# pcb_inverter_final.net
KiCad netlist of a schematic drawn in EAGLE
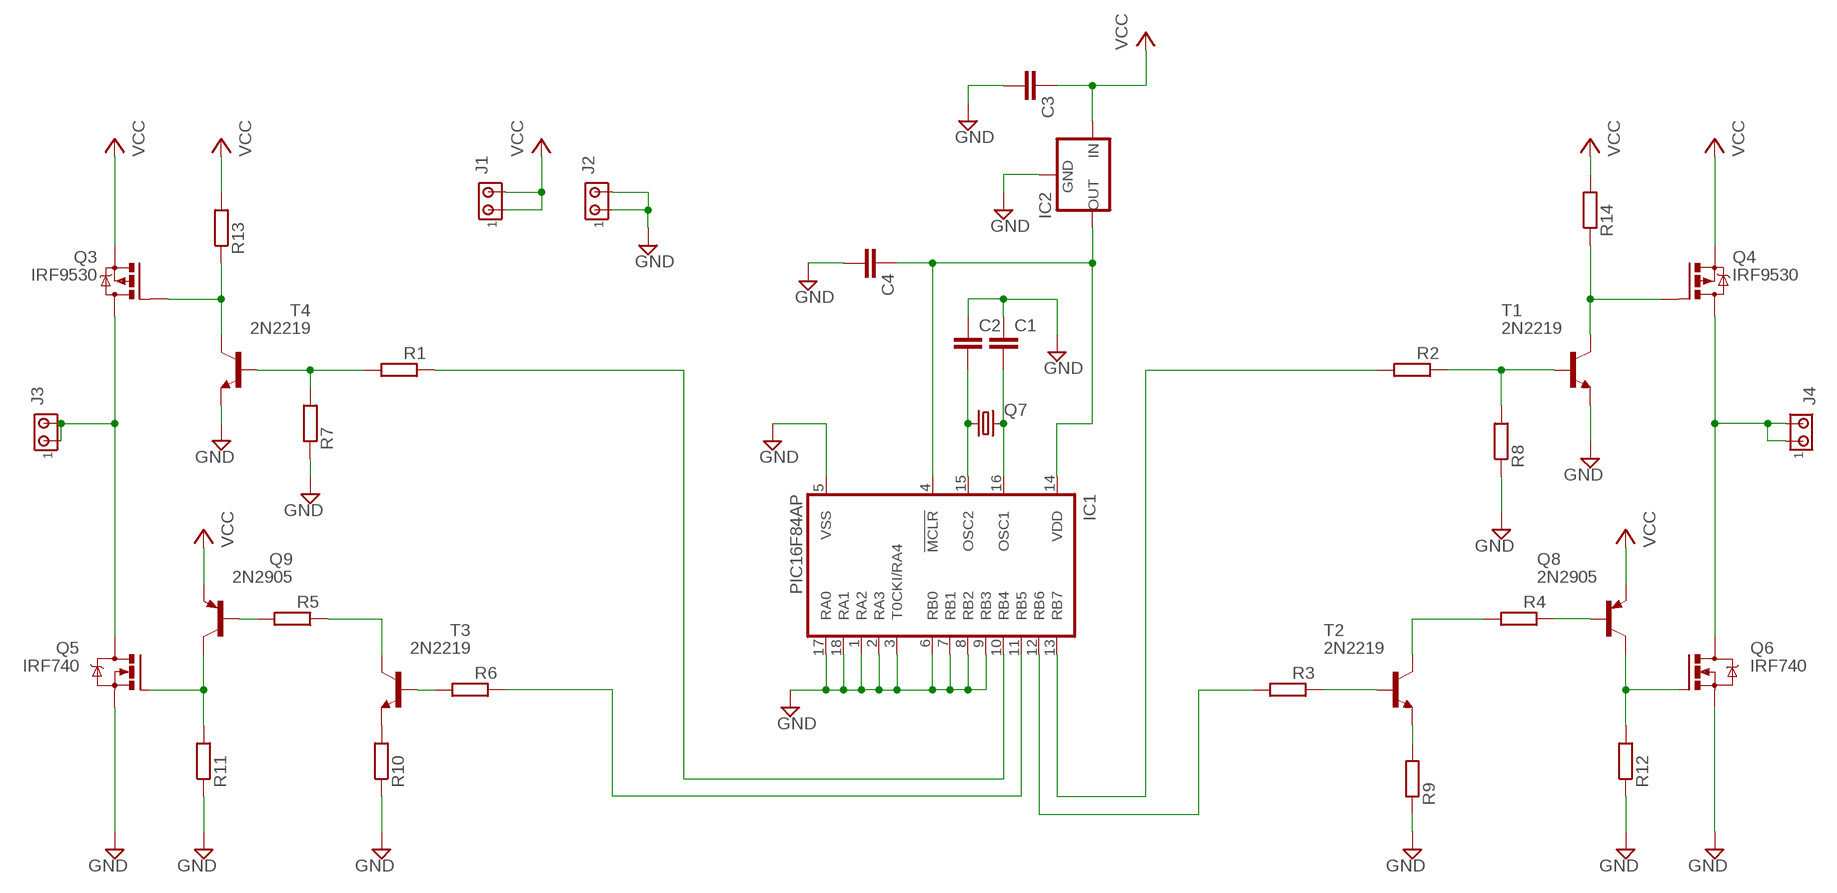
[diagram p0: schematic, sheet 1]

(export (version "E")
  (design (tool "Eeschema 10.0.6"))
  (components
    (comp (ref "C1")
      (value "C2.5/5")
      (footprint "eagle-import:C2.5-5")
      (libsource (lib "eagle-import") (part "C2.5/5"))
    )
    (comp (ref "C2")
      (value "C2.5/5")
      (footprint "eagle-import:C2.5-5")
      (libsource (lib "eagle-import") (part "C2.5/5"))
    )
    (comp (ref "C3")
      (value "C2.5/5")
      (footprint "eagle-import:C2.5-5")
      (libsource (lib "eagle-import") (part "C2.5/5"))
    )
    (comp (ref "C4")
      (value "C2.5/5")
      (footprint "eagle-import:C2.5-5")
      (libsource (lib "eagle-import") (part "C2.5/5"))
    )
    (comp (ref "IC1")
      (value "PIC16F84AP")
      (footprint "eagle-import:DIL18")
      (fields (field (name "MF") "MICROCHIP") (field (name "MPN") "PIC16F84A-04I/P"))
      (libsource (lib "eagle-import") (part "PIC16F8P4A"))
    )
    (comp (ref "IC2")
      (value "78XXS")
      (footprint "eagle-import:78XXS")
      (libsource (lib "eagle-import") (part "78XXS"))
    )
    (comp (ref "J1")
      (value "MTA02-156")
      (footprint "eagle-import:1X2MTA")
      (libsource (lib "eagle-import") (part "MTA02-156"))
    )
    (comp (ref "J2")
      (value "MTA02-156")
      (footprint "eagle-import:1X2MTA")
      (libsource (lib "eagle-import") (part "MTA02-156"))
    )
    (comp (ref "J3")
      (value "MTA02-156")
      (footprint "eagle-import:1X2MTA")
      (libsource (lib "eagle-import") (part "MTA02-156"))
    )
    (comp (ref "J4")
      (value "MTA02-156")
      (footprint "eagle-import:1X2MTA")
      (libsource (lib "eagle-import") (part "MTA02-156"))
    )
    (comp (ref "Q3")
      (value "IRF9530")
      (footprint "eagle-import:TO220BV")
      (libsource (lib "eagle-import") (part "IRF9530"))
    )
    (comp (ref "Q4")
      (value "IRF9530")
      (footprint "eagle-import:TO220BV")
      (libsource (lib "eagle-import") (part "IRF9530"))
    )
    (comp (ref "Q5")
      (value "IRF740")
      (footprint "eagle-import:TO220BV")
      (libsource (lib "eagle-import") (part "IRF740"))
    )
    (comp (ref "Q6")
      (value "IRF740")
      (footprint "eagle-import:TO220BV")
      (libsource (lib "eagle-import") (part "IRF740"))
    )
    (comp (ref "Q7")
      (value "CRYSTALHC18U-V")
      (footprint "eagle-import:HC18U-V")
      (libsource (lib "eagle-import") (part "CRYSTALHC18U-V"))
    )
    (comp (ref "Q8")
      (value "2N2905")
      (footprint "eagle-import:TO5")
      (libsource (lib "eagle-import") (part "2N2905"))
    )
    (comp (ref "Q9")
      (value "2N2905")
      (footprint "eagle-import:TO5")
      (libsource (lib "eagle-import") (part "2N2905"))
    )
    (comp (ref "R1")
      (value "R-EU_0204/7")
      (footprint "eagle-import:0204_7")
      (libsource (lib "eagle-import") (part "R-EU_0204/7"))
    )
    (comp (ref "R2")
      (value "R-EU_0204/7")
      (footprint "eagle-import:0204_7")
      (libsource (lib "eagle-import") (part "R-EU_0204/7"))
    )
    (comp (ref "R3")
      (value "R-EU_0204/7")
      (footprint "eagle-import:0204_7")
      (libsource (lib "eagle-import") (part "R-EU_0204/7"))
    )
    (comp (ref "R4")
      (value "R-EU_0204/7")
      (footprint "eagle-import:0204_7")
      (libsource (lib "eagle-import") (part "R-EU_0204/7"))
    )
    (comp (ref "R5")
      (value "R-EU_0204/7")
      (footprint "eagle-import:0204_7")
      (libsource (lib "eagle-import") (part "R-EU_0204/7"))
    )
    (comp (ref "R6")
      (value "R-EU_0204/7")
      (footprint "eagle-import:0204_7")
      (libsource (lib "eagle-import") (part "R-EU_0204/7"))
    )
    (comp (ref "R7")
      (value "R-EU_0204/7")
      (footprint "eagle-import:0204_7")
      (libsource (lib "eagle-import") (part "R-EU_0204/7"))
    )
    (comp (ref "R8")
      (value "R-EU_0204/7")
      (footprint "eagle-import:0204_7")
      (libsource (lib "eagle-import") (part "R-EU_0204/7"))
    )
    (comp (ref "R9")
      (value "R-EU_0204/7")
      (footprint "eagle-import:0204_7")
      (libsource (lib "eagle-import") (part "R-EU_0204/7"))
    )
    (comp (ref "R10")
      (value "R-EU_0204/7")
      (footprint "eagle-import:0204_7")
      (libsource (lib "eagle-import") (part "R-EU_0204/7"))
    )
    (comp (ref "R11")
      (value "R-EU_0204/7")
      (footprint "eagle-import:0204_7")
      (libsource (lib "eagle-import") (part "R-EU_0204/7"))
    )
    (comp (ref "R12")
      (value "R-EU_0204/7")
      (footprint "eagle-import:0204_7")
      (libsource (lib "eagle-import") (part "R-EU_0204/7"))
    )
    (comp (ref "R13")
      (value "R-EU_0204/7")
      (footprint "eagle-import:0204_7")
      (libsource (lib "eagle-import") (part "R-EU_0204/7"))
    )
    (comp (ref "R14")
      (value "R-EU_0204/7")
      (footprint "eagle-import:0204_7")
      (libsource (lib "eagle-import") (part "R-EU_0204/7"))
    )
    (comp (ref "T1")
      (value "2N2219")
      (footprint "eagle-import:TO5")
      (libsource (lib "eagle-import") (part "2N2219"))
    )
    (comp (ref "T2")
      (value "2N2219")
      (footprint "eagle-import:TO5")
      (libsource (lib "eagle-import") (part "2N2219"))
    )
    (comp (ref "T3")
      (value "2N2219")
      (footprint "eagle-import:TO5")
      (libsource (lib "eagle-import") (part "2N2219"))
    )
    (comp (ref "T4")
      (value "2N2219")
      (footprint "eagle-import:TO5")
      (libsource (lib "eagle-import") (part "2N2219"))
    )
  )
  (nets
    (net (code "1") (name "GND") (class "Default")
      (node (ref "C1") (pin "1") (pinfunction "1_1") (pintype "passive"))
      (node (ref "C2") (pin "1") (pinfunction "1_1") (pintype "passive"))
      (node (ref "C3") (pin "2") (pinfunction "2_2") (pintype "passive"))
      (node (ref "C4") (pin "2") (pinfunction "2_2") (pintype "passive"))
      (node (ref "IC1") (pin "1") (pinfunction "RA2_1") (pintype "bidirectional"))
      (node (ref "IC1") (pin "17") (pinfunction "RA0_17") (pintype "bidirectional"))
      (node (ref "IC1") (pin "18") (pinfunction "RA1_18") (pintype "bidirectional"))
      (node (ref "IC1") (pin "2") (pinfunction "RA3_2") (pintype "bidirectional"))
      (node (ref "IC1") (pin "3") (pinfunction "T0CKI/RA4_3") (pintype "bidirectional"))
      (node (ref "IC1") (pin "5") (pinfunction "VSS_5") (pintype "power_in"))
      (node (ref "IC1") (pin "6") (pinfunction "RB0_6") (pintype "bidirectional"))
      (node (ref "IC1") (pin "7") (pinfunction "RB1_7") (pintype "bidirectional"))
      (node (ref "IC1") (pin "8") (pinfunction "RB2_8") (pintype "bidirectional"))
      (node (ref "IC1") (pin "9") (pinfunction "RB3_9") (pintype "bidirectional"))
      (node (ref "IC2") (pin "GND") (pinfunction "GND_GND") (pintype "input"))
      (node (ref "J2") (pin "1") (pinfunction "1_1") (pintype "passive"))
      (node (ref "J2") (pin "2") (pinfunction "2_2") (pintype "passive"))
      (node (ref "Q5") (pin "S") (pinfunction "S_S") (pintype "passive"))
      (node (ref "Q6") (pin "S") (pinfunction "S_S") (pintype "passive"))
      (node (ref "R10") (pin "1") (pinfunction "1_1") (pintype "passive"))
      (node (ref "R11") (pin "1") (pinfunction "1_1") (pintype "passive"))
      (node (ref "R12") (pin "1") (pinfunction "1_1") (pintype "passive"))
      (node (ref "R7") (pin "1") (pinfunction "1_1") (pintype "passive"))
      (node (ref "R8") (pin "1") (pinfunction "1_1") (pintype "passive"))
      (node (ref "R9") (pin "1") (pinfunction "1_1") (pintype "passive"))
      (node (ref "T1") (pin "1") (pinfunction "E_1") (pintype "passive"))
      (node (ref "T4") (pin "1") (pinfunction "E_1") (pintype "passive"))
    )
    (net (code "2") (name "Net-(IC1-OSC1)") (class "Default")
      (node (ref "C1") (pin "2") (pinfunction "2_2") (pintype "passive"))
      (node (ref "IC1") (pin "16") (pinfunction "OSC1_16") (pintype "input"))
      (node (ref "Q7") (pin "2") (pinfunction "2_2") (pintype "passive"))
    )
    (net (code "3") (name "Net-(IC1-OSC2)") (class "Default")
      (node (ref "C2") (pin "2") (pinfunction "2_2") (pintype "passive"))
      (node (ref "IC1") (pin "15") (pinfunction "OSC2_15") (pintype "output"))
      (node (ref "Q7") (pin "1") (pinfunction "1_1") (pintype "passive"))
    )
    (net (code "4") (name "Net-(IC1-RB4)") (class "Default")
      (node (ref "IC1") (pin "10") (pinfunction "RB4_10") (pintype "bidirectional"))
      (node (ref "R1") (pin "1") (pinfunction "1_1") (pintype "passive"))
    )
    (net (code "5") (name "Net-(IC1-RB5)") (class "Default")
      (node (ref "IC1") (pin "11") (pinfunction "RB5_11") (pintype "bidirectional"))
      (node (ref "R6") (pin "1") (pinfunction "1_1") (pintype "passive"))
    )
    (net (code "6") (name "Net-(IC1-RB6)") (class "Default")
      (node (ref "IC1") (pin "12") (pinfunction "RB6_12") (pintype "bidirectional"))
      (node (ref "R3") (pin "2") (pinfunction "2_2") (pintype "passive"))
    )
    (net (code "7") (name "Net-(IC1-RB7)") (class "Default")
      (node (ref "IC1") (pin "13") (pinfunction "RB7_13") (pintype "bidirectional"))
      (node (ref "R2") (pin "2") (pinfunction "2_2") (pintype "passive"))
    )
    (net (code "8") (name "Net-(IC1-VDD)") (class "Default")
      (node (ref "C4") (pin "1") (pinfunction "1_1") (pintype "passive"))
      (node (ref "IC1") (pin "14") (pinfunction "VDD_14") (pintype "power_in"))
      (node (ref "IC1") (pin "4") (pinfunction "~{MCLR}_4") (pintype "input"))
      (node (ref "IC2") (pin "OUT") (pinfunction "OUT_OUT") (pintype "passive"))
    )
    (net (code "9") (name "Net-(J3-Pad1)") (class "Default")
      (node (ref "J3") (pin "1") (pinfunction "1_1") (pintype "passive"))
      (node (ref "J3") (pin "2") (pinfunction "2_2") (pintype "passive"))
      (node (ref "Q3") (pin "D") (pinfunction "D_D") (pintype "passive"))
      (node (ref "Q5") (pin "D") (pinfunction "D_D") (pintype "passive"))
    )
    (net (code "10") (name "Net-(J4-Pad1)") (class "Default")
      (node (ref "J4") (pin "1") (pinfunction "1_1") (pintype "passive"))
      (node (ref "J4") (pin "2") (pinfunction "2_2") (pintype "passive"))
      (node (ref "Q4") (pin "D") (pinfunction "D_D") (pintype "passive"))
      (node (ref "Q6") (pin "D") (pinfunction "D_D") (pintype "passive"))
    )
    (net (code "11") (name "Net-(Q8-B)") (class "Default")
      (node (ref "Q8") (pin "2") (pinfunction "B_2") (pintype "passive"))
      (node (ref "R4") (pin "1") (pinfunction "1_1") (pintype "passive"))
    )
    (net (code "12") (name "Net-(Q8-C)") (class "Default")
      (node (ref "Q6") (pin "G") (pinfunction "G_G") (pintype "passive"))
      (node (ref "Q8") (pin "3") (pinfunction "C_3") (pintype "passive"))
      (node (ref "R12") (pin "2") (pinfunction "2_2") (pintype "passive"))
    )
    (net (code "13") (name "Net-(Q9-B)") (class "Default")
      (node (ref "Q9") (pin "2") (pinfunction "B_2") (pintype "passive"))
      (node (ref "R5") (pin "2") (pinfunction "2_2") (pintype "passive"))
    )
    (net (code "14") (name "Net-(Q9-C)") (class "Default")
      (node (ref "Q5") (pin "G") (pinfunction "G_G") (pintype "passive"))
      (node (ref "Q9") (pin "3") (pinfunction "C_3") (pintype "passive"))
      (node (ref "R11") (pin "2") (pinfunction "2_2") (pintype "passive"))
    )
    (net (code "15") (name "Net-(T1-B)") (class "Default")
      (node (ref "R2") (pin "1") (pinfunction "1_1") (pintype "passive"))
      (node (ref "R8") (pin "2") (pinfunction "2_2") (pintype "passive"))
      (node (ref "T1") (pin "2") (pinfunction "B_2") (pintype "passive"))
    )
    (net (code "16") (name "Net-(T1-C)") (class "Default")
      (node (ref "Q4") (pin "G") (pinfunction "G_G") (pintype "passive"))
      (node (ref "R14") (pin "1") (pinfunction "1_1") (pintype "passive"))
      (node (ref "T1") (pin "3") (pinfunction "C_3") (pintype "passive"))
    )
    (net (code "17") (name "Net-(T2-B)") (class "Default")
      (node (ref "R3") (pin "1") (pinfunction "1_1") (pintype "passive"))
      (node (ref "T2") (pin "2") (pinfunction "B_2") (pintype "passive"))
    )
    (net (code "18") (name "Net-(T2-C)") (class "Default")
      (node (ref "R4") (pin "2") (pinfunction "2_2") (pintype "passive"))
      (node (ref "T2") (pin "3") (pinfunction "C_3") (pintype "passive"))
    )
    (net (code "19") (name "Net-(T2-E)") (class "Default")
      (node (ref "R9") (pin "2") (pinfunction "2_2") (pintype "passive"))
      (node (ref "T2") (pin "1") (pinfunction "E_1") (pintype "passive"))
    )
    (net (code "20") (name "Net-(T3-B)") (class "Default")
      (node (ref "R6") (pin "2") (pinfunction "2_2") (pintype "passive"))
      (node (ref "T3") (pin "2") (pinfunction "B_2") (pintype "passive"))
    )
    (net (code "21") (name "Net-(T3-C)") (class "Default")
      (node (ref "R5") (pin "1") (pinfunction "1_1") (pintype "passive"))
      (node (ref "T3") (pin "3") (pinfunction "C_3") (pintype "passive"))
    )
    (net (code "22") (name "Net-(T3-E)") (class "Default")
      (node (ref "R10") (pin "2") (pinfunction "2_2") (pintype "passive"))
      (node (ref "T3") (pin "1") (pinfunction "E_1") (pintype "passive"))
    )
    (net (code "23") (name "Net-(T4-B)") (class "Default")
      (node (ref "R1") (pin "2") (pinfunction "2_2") (pintype "passive"))
      (node (ref "R7") (pin "2") (pinfunction "2_2") (pintype "passive"))
      (node (ref "T4") (pin "2") (pinfunction "B_2") (pintype "passive"))
    )
    (net (code "24") (name "Net-(T4-C)") (class "Default")
      (node (ref "Q3") (pin "G") (pinfunction "G_G") (pintype "passive"))
      (node (ref "R13") (pin "1") (pinfunction "1_1") (pintype "passive"))
      (node (ref "T4") (pin "3") (pinfunction "C_3") (pintype "passive"))
    )
    (net (code "25") (name "VCC") (class "Default")
      (node (ref "C3") (pin "1") (pinfunction "1_1") (pintype "passive"))
      (node (ref "IC2") (pin "IN") (pinfunction "IN_IN") (pintype "input"))
      (node (ref "J1") (pin "1") (pinfunction "1_1") (pintype "passive"))
      (node (ref "J1") (pin "2") (pinfunction "2_2") (pintype "passive"))
      (node (ref "Q3") (pin "S") (pinfunction "S_S") (pintype "passive"))
      (node (ref "Q4") (pin "S") (pinfunction "S_S") (pintype "passive"))
      (node (ref "Q8") (pin "1") (pinfunction "E_1") (pintype "passive"))
      (node (ref "Q9") (pin "1") (pinfunction "E_1") (pintype "passive"))
      (node (ref "R13") (pin "2") (pinfunction "2_2") (pintype "passive"))
      (node (ref "R14") (pin "2") (pinfunction "2_2") (pintype "passive"))
    )
  )
)
